# STM32_BOARD_v1a_main.net
KiCad netlist of a schematic drawn in Altium Designer
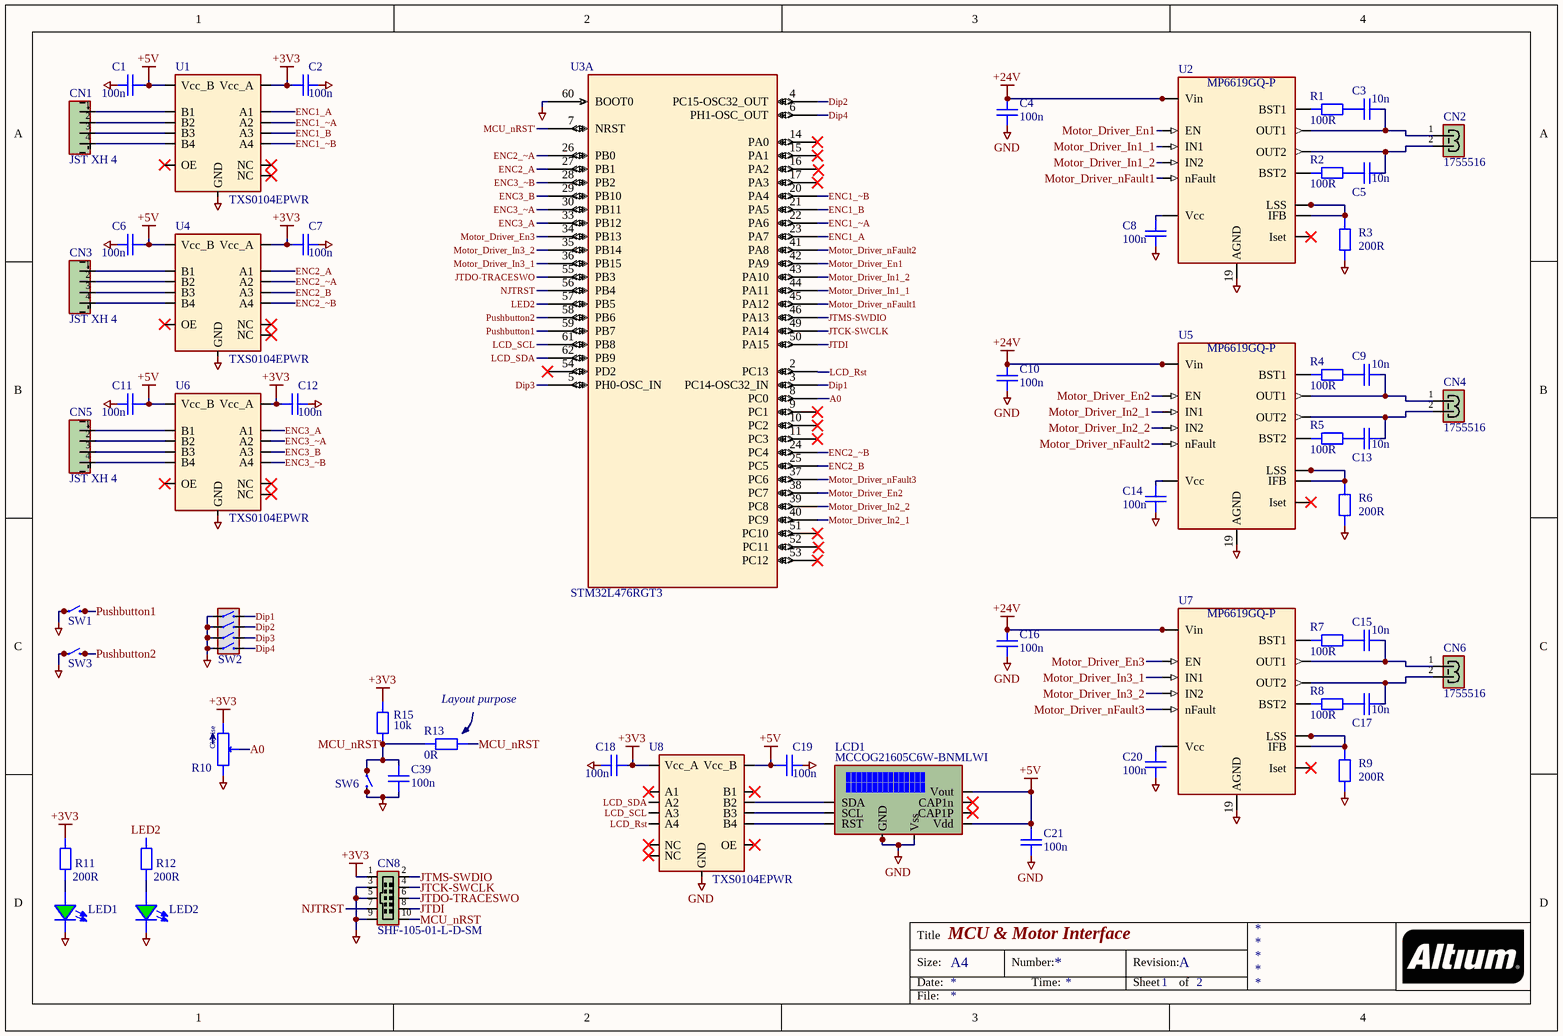
[diagram p0: STM32_BOARD_v1a_main.SchDoc]

(export (version "E")
  (design (tool "Eeschema 10.0.6"))
  (components
    (comp (ref "C1") (value "100n") (footprint "CAP_SMD") (libsource (lib "Miscellanous") (part "C")))
    (comp (ref "C2") (value "100n") (footprint "CAP_SMD") (libsource (lib "Miscellanous") (part "C")))
    (comp (ref "C3") (value "10n") (footprint "CAP_SMD") (libsource (lib "Miscellanous") (part "C")))
    (comp (ref "C4") (value "100n") (footprint "CAP_SMD") (libsource (lib "Miscellanous") (part "C")))
    (comp (ref "C5") (value "10n") (footprint "CAP_SMD") (libsource (lib "Miscellanous") (part "C")))
    (comp (ref "C6") (value "100n") (footprint "CAP_SMD") (libsource (lib "Miscellanous") (part "C")))
    (comp (ref "C7") (value "100n") (footprint "CAP_SMD") (libsource (lib "Miscellanous") (part "C")))
    (comp (ref "C8") (value "100n") (footprint "CAP_SMD") (libsource (lib "Miscellanous") (part "C")))
    (comp (ref "C9") (value "10n") (footprint "CAP_SMD") (libsource (lib "Miscellanous") (part "C")))
    (comp (ref "C10") (value "100n") (footprint "CAP_SMD") (libsource (lib "Miscellanous") (part "C")))
    (comp (ref "C11") (value "100n") (footprint "CAP_SMD") (libsource (lib "Miscellanous") (part "C")))
    (comp (ref "C12") (value "100n") (footprint "CAP_SMD") (libsource (lib "Miscellanous") (part "C")))
    (comp (ref "C13") (value "10n") (footprint "CAP_SMD") (libsource (lib "Miscellanous") (part "C")))
    (comp (ref "C14") (value "100n") (footprint "CAP_SMD") (libsource (lib "Miscellanous") (part "C")))
    (comp (ref "C15") (value "10n") (footprint "CAP_SMD") (libsource (lib "Miscellanous") (part "C")))
    (comp (ref "C16") (value "100n") (footprint "CAP_SMD") (libsource (lib "Miscellanous") (part "C")))
    (comp (ref "C17") (value "10n") (footprint "CAP_SMD") (libsource (lib "Miscellanous") (part "C")))
    (comp (ref "C18") (value "100n") (footprint "CAP_SMD") (libsource (lib "Miscellanous") (part "C")))
    (comp (ref "C19") (value "100n") (footprint "CAP_SMD") (libsource (lib "Miscellanous") (part "C")))
    (comp (ref "C20") (value "100n") (footprint "CAP_SMD") (libsource (lib "Miscellanous") (part "C")))
    (comp (ref "C21") (value "100n") (footprint "CAP_SMD") (libsource (lib "Miscellanous") (part "C")))
    (comp (ref "C39") (value "100n") (footprint "CAP_SMD") (libsource (lib "Miscellanous") (part "C")))
    (comp (ref "CN1")
      (value "JST XH 4")
      (footprint "JST_XH_4-PIN")
      (description "JST XH 4 Pin Connector")
      (fields (field (name "MANUFACTURER") "JASO"))
      (libsource (lib "Connectors") (part "JST_XH_4_PIN"))
    )
    (comp (ref "CN2")
      (value "PHOENIX_CONTACT_2x1_")
      (footprint "1755516")
      (description "Pin header, straight, Straight, 5mm Pitch, 2 Poles, Phoenix Contact")
      (fields (field (name "MANUFACTURER") "Phoenix Contact") (field (name "MFR PART NUM.") "1755516"))
      (libsource (lib "Connectors") (part "PHOENIX_CONTACT_2x1_"))
    )
    (comp (ref "CN3")
      (value "JST XH 4")
      (footprint "JST_XH_4-PIN")
      (description "JST XH 4 Pin Connector")
      (fields (field (name "MANUFACTURER") "JASO"))
      (libsource (lib "Connectors") (part "JST_XH_4_PIN"))
    )
    (comp (ref "CN4")
      (value "PHOENIX_CONTACT_2x1_")
      (footprint "1755516")
      (description "Pin header, straight, Straight, 5mm Pitch, 2 Poles, Phoenix Contact")
      (fields (field (name "MANUFACTURER") "Phoenix Contact") (field (name "MFR PART NUM.") "1755516"))
      (libsource (lib "Connectors") (part "PHOENIX_CONTACT_2x1_"))
    )
    (comp (ref "CN5")
      (value "JST XH 4")
      (footprint "JST_XH_4-PIN")
      (description "JST XH 4 Pin Connector")
      (fields (field (name "MANUFACTURER") "JASO"))
      (libsource (lib "Connectors") (part "JST_XH_4_PIN"))
    )
    (comp (ref "CN6")
      (value "PHOENIX_CONTACT_2x1_")
      (footprint "1755516")
      (description "Pin header, straight, Straight, 5mm Pitch, 2 Poles, Phoenix Contact")
      (fields (field (name "MANUFACTURER") "Phoenix Contact") (field (name "MFR PART NUM.") "1755516"))
      (libsource (lib "Connectors") (part "PHOENIX_CONTACT_2x1_"))
    )
    (comp (ref "CN8")
      (value "SHF-105-01-L-D-SM")
      (footprint "SHF-105-01-L-D-SM")
      (description "Pin Header, Vertical, Wire-to-Board, 1.27 mm, 2 Rows, 10 Contacts, Surface Mount, SHF")
      (fields (field (name "MANUFACTURER") "Samtec"))
      (libsource (lib "Connectors") (part "SHF-105-01-L-D-SM"))
    )
    (comp (ref "LCD1")
      (value "MCCOG21605C6W-BNMLWI")
      (footprint "MCCOG21605C6W-BNMLWI")
      (description "Alphanumeric LCD, 16 x 2, White on Blue, 3V to 5V, I2C, English, Japanese, Transmissive")
      (fields (field (name "MANUFACTURER") "MIDAS"))
      (libsource (lib "Various") (part "MCCOG21605C6W-BNMLWI"))
    )
    (comp (ref "LED1")
      (value "LED_SMD_GREEN")
      (footprint "LED_0805_GREEN")
      (libsource (lib "Miscellanous") (part "LED_SMD_GREEN"))
    )
    (comp (ref "LED2")
      (value "LED_SMD_GREEN")
      (footprint "LED_0805_GREEN")
      (libsource (lib "Miscellanous") (part "LED_SMD_GREEN"))
    )
    (comp (ref "R1") (value "100R") (footprint "RES_0805") (libsource (lib "Miscellanous") (part "R")))
    (comp (ref "R2") (value "100R") (footprint "RES_0805") (libsource (lib "") (part "R_1")))
    (comp (ref "R3") (value "200R") (footprint "RES_0805") (libsource (lib "Miscellanous") (part "R")))
    (comp (ref "R4") (value "100R") (footprint "RES_0805") (libsource (lib "Miscellanous") (part "R")))
    (comp (ref "R5") (value "100R") (footprint "RES_0805") (libsource (lib "") (part "R_1")))
    (comp (ref "R6") (value "200R") (footprint "RES_0805") (libsource (lib "Miscellanous") (part "R")))
    (comp (ref "R7") (value "100R") (footprint "RES_0805") (libsource (lib "Miscellanous") (part "R")))
    (comp (ref "R8") (value "100R") (footprint "RES_0805") (libsource (lib "") (part "R_1")))
    (comp (ref "R9") (value "200R") (footprint "RES_0805") (libsource (lib "Miscellanous") (part "R")))
    (comp (ref "R10")
      (value "TC33X-2-502E")
      (footprint "TC33X-2")
      (description "Trimpot, Single Turn, Cermet, Top Adjust, 5 kohm, Surface Mount, 1 Turns")
      (fields (field (name "MANUFACTURER") "Bourns"))
      (libsource (lib "Various") (part "TC33X-2-502E"))
    )
    (comp (ref "R11") (value "200R") (footprint "RES_0805") (libsource (lib "") (part "R_1")))
    (comp (ref "R12") (value "200R") (footprint "RES_0805") (libsource (lib "") (part "R_1")))
    (comp (ref "R13") (value "0R") (footprint "RES_0805") (libsource (lib "") (part "R_2")))
    (comp (ref "R15") (value "10k") (footprint "RES_0805") (libsource (lib "") (part "R_1")))
    (comp (ref "SW1")
      (value "PTS645SM43SMTR92LFS")
      (footprint "Pushbutton_6x6mm")
      (description "Tactile Switch, PT645, Top Actuated, Surface Mount, Round Button, 160 gf, 50mA at 12VDC")
      (fields (field (name "MANUFACTURER") "C&K Components") (field (name "VOLTAGE") "12V"))
      (libsource (lib "Various") (part "PTS645SM43SMTR92LFS"))
    )
    (comp (ref "SW2")
      (value "A6H-4101")
      (footprint "A6H-4101")
      (description "DIP / SIP Switch, 4 Circuits, Slide, Surface Mount, SPST, 24 VDC, 25 mA")
      (fields (field (name "MANUFACTURER") "Omron") (field (name "VOLTAGE") "24V"))
      (libsource (lib "Various") (part "A6H-4101"))
    )
    (comp (ref "SW3")
      (value "PTS645SM43SMTR92LFS")
      (footprint "Pushbutton_6x6mm")
      (description "Tactile Switch, PT645, Top Actuated, Surface Mount, Round Button, 160 gf, 50mA at 12VDC")
      (fields (field (name "MANUFACTURER") "C&K Components") (field (name "VOLTAGE") "12V"))
      (libsource (lib "Various") (part "PTS645SM43SMTR92LFS"))
    )
    (comp (ref "SW6")
      (value "PTS645SM43SMTR92LFS")
      (footprint "Pushbutton_6x6mm")
      (description "Tactile Switch, PT645, Top Actuated, Surface Mount, Round Button, 160 gf, 50mA at 12VDC")
      (fields (field (name "MANUFACTURER") "C&K Components") (field (name "VOLTAGE") "12V"))
      (libsource (lib "Various") (part "PTS645SM43SMTR92LFS"))
    )
    (comp (ref "U1")
      (value "TXS0104EPWR")
      (footprint "TSOP65P640X120-14N")
      (description "Voltage Level Translator, 4 Input, 50 mA, 4.6 ns, 1.65 V to 5.5 V, TSSOP-14")
      (fields (field (name "MANUFACTURER") "Texas Instruments") (field (name "MFR PART NUM.") "TXS0104EPWR"))
      (libsource (lib "IC_Digital") (part "TXS0104E"))
    )
    (comp (ref "U2")
      (value "MP6619GQ-P")
      (footprint "MP6619GQ-P")
      (description "H-Bridge Motor driver")
      (fields (field (name "MANUFACTURER") "MPS") (field (name "MFR PART NUM") "MP6619GQ-P"))
      (libsource (lib "IC_Digital") (part "MP6619GQ-P"))
    )
    (comp (ref "U3")
      (value "32-bit Microcontroller")
      (footprint "LQFP64_10x10mm")
      (description "STM32 Arm-based 32-bit Microcontroller")
      (fields
        (field (name "MFR PART NUM") "STM32L476RGT3")
        (field (name "MANUFACTURER") "STMicroelectronics")
      )
      (libsource (lib "IC_Digital") (part "STM32L476RGT3"))
    )
    (comp (ref "U4")
      (value "TXS0104EPWR")
      (footprint "TSOP65P640X120-14N")
      (description "Voltage Level Translator, 4 Input, 50 mA, 4.6 ns, 1.65 V to 5.5 V, TSSOP-14")
      (fields (field (name "MANUFACTURER") "Texas Instruments") (field (name "MFR PART NUM.") "TXS0104EPWR"))
      (libsource (lib "IC_Digital") (part "TXS0104E"))
    )
    (comp (ref "U5")
      (value "MP6619GQ-P")
      (footprint "MP6619GQ-P")
      (description "H-Bridge Motor driver")
      (fields (field (name "MANUFACTURER") "MPS") (field (name "MFR PART NUM") "MP6619GQ-P"))
      (libsource (lib "IC_Digital") (part "MP6619GQ-P"))
    )
    (comp (ref "U6")
      (value "TXS0104EPWR")
      (footprint "TSOP65P640X120-14N")
      (description "Voltage Level Translator, 4 Input, 50 mA, 4.6 ns, 1.65 V to 5.5 V, TSSOP-14")
      (fields (field (name "MANUFACTURER") "Texas Instruments") (field (name "MFR PART NUM.") "TXS0104EPWR"))
      (libsource (lib "IC_Digital") (part "TXS0104E"))
    )
    (comp (ref "U7")
      (value "MP6619GQ-P")
      (footprint "MP6619GQ-P")
      (description "H-Bridge Motor driver")
      (fields (field (name "MANUFACTURER") "MPS") (field (name "MFR PART NUM") "MP6619GQ-P"))
      (libsource (lib "IC_Digital") (part "MP6619GQ-P"))
    )
    (comp (ref "U8")
      (value "TXS0104EPWR")
      (footprint "TSOP65P640X120-14N")
      (description "Voltage Level Translator, 4 Input, 50 mA, 4.6 ns, 1.65 V to 5.5 V, TSSOP-14")
      (fields (field (name "MANUFACTURER") "Texas Instruments") (field (name "MFR PART NUM.") "TXS0104EPWR"))
      (libsource (lib "") (part "TXS0104E_1"))
    )
  )
  (nets
    (net (code "1") (name "+3V3") (class "Default")
      (node (ref "C12") (pin "2") (pinfunction "Pin_2_2") (pintype "passive"))
      (node (ref "C18") (pin "2") (pinfunction "Pin_2_2") (pintype "passive"))
      (node (ref "C2") (pin "2") (pinfunction "Pin_2_2") (pintype "passive"))
      (node (ref "C7") (pin "2") (pinfunction "Pin_2_2") (pintype "passive"))
      (node (ref "CN8") (pin "1") (pinfunction "Pin1_1") (pintype "power_in"))
      (node (ref "R10") (pin "3") (pinfunction "Pin_3_3") (pintype "power_in"))
      (node (ref "R11") (pin "2") (pinfunction "Pin_2_2") (pintype "passive"))
      (node (ref "R15") (pin "2") (pinfunction "Pin_2_2") (pintype "passive"))
      (node (ref "U1") (pin "1") (pinfunction "Vcc_A_1") (pintype "power_in"))
      (node (ref "U4") (pin "1") (pinfunction "Vcc_A_1") (pintype "power_in"))
      (node (ref "U6") (pin "1") (pinfunction "Vcc_A_1") (pintype "power_in"))
      (node (ref "U8") (pin "1") (pinfunction "Vcc_A_1") (pintype "power_in"))
    )
    (net (code "2") (name "+5V") (class "Default")
      (node (ref "C1") (pin "2") (pinfunction "Pin_2_2") (pintype "passive"))
      (node (ref "C11") (pin "2") (pinfunction "Pin_2_2") (pintype "passive"))
      (node (ref "C19") (pin "2") (pinfunction "Pin_2_2") (pintype "passive"))
      (node (ref "C21") (pin "2") (pinfunction "Pin_2_2") (pintype "passive"))
      (node (ref "C6") (pin "2") (pinfunction "Pin_2_2") (pintype "passive"))
      (node (ref "LCD1") (pin "1") (pinfunction "Vout_1") (pintype "power_in"))
      (node (ref "LCD1") (pin "4") (pinfunction "Vdd_4") (pintype "power_in"))
      (node (ref "U1") (pin "14") (pinfunction "Vcc_B_14") (pintype "power_in"))
      (node (ref "U4") (pin "14") (pinfunction "Vcc_B_14") (pintype "power_in"))
      (node (ref "U6") (pin "14") (pinfunction "Vcc_B_14") (pintype "power_in"))
      (node (ref "U8") (pin "14") (pinfunction "Vcc_B_14") (pintype "power_in"))
    )
    (net (code "3") (name "+24V") (class "Default")
      (node (ref "C10") (pin "2") (pinfunction "Pin_2_2") (pintype "passive"))
      (node (ref "C16") (pin "2") (pinfunction "Pin_2_2") (pintype "passive"))
      (node (ref "C4") (pin "2") (pinfunction "Pin_2_2") (pintype "passive"))
      (node (ref "U2") (pin "11") (pinfunction "Vin_11") (pintype "power_in"))
      (node (ref "U2") (pin "2") (pinfunction "Vin_2") (pintype "power_in"))
      (node (ref "U5") (pin "11") (pinfunction "Vin_11") (pintype "power_in"))
      (node (ref "U5") (pin "2") (pinfunction "Vin_2") (pintype "power_in"))
      (node (ref "U7") (pin "11") (pinfunction "Vin_11") (pintype "power_in"))
      (node (ref "U7") (pin "2") (pinfunction "Vin_2") (pintype "power_in"))
    )
    (net (code "4") (name "/A0") (class "Default")
      (node (ref "R10") (pin "2") (pinfunction "Pin_2_2") (pintype "power_in"))
      (node (ref "U3") (pin "8") (pinfunction "PC0_8") (pintype "bidirectional"))
    )
    (net (code "5") (name "/Dip1") (class "Default")
      (node (ref "SW2") (pin "8") (pinfunction "Pin_8_8") (pintype "passive"))
      (node (ref "U3") (pin "3") (pinfunction "PC14-OSC32_IN_3") (pintype "bidirectional"))
    )
    (net (code "6") (name "/Dip2") (class "Default")
      (node (ref "SW2") (pin "7") (pinfunction "Pin_7_7") (pintype "passive"))
      (node (ref "U3") (pin "4") (pinfunction "PC15-OSC32_OUT_4") (pintype "bidirectional"))
    )
    (net (code "7") (name "/Dip3") (class "Default")
      (node (ref "SW2") (pin "6") (pinfunction "Pin_6_6") (pintype "passive"))
      (node (ref "U3") (pin "5") (pinfunction "PH0-OSC_IN_5") (pintype "bidirectional"))
    )
    (net (code "8") (name "/Dip4") (class "Default")
      (node (ref "SW2") (pin "5") (pinfunction "Pin_5_5") (pintype "passive"))
      (node (ref "U3") (pin "6") (pinfunction "PH1-OSC_OUT_6") (pintype "bidirectional"))
    )
    (net (code "9") (name "/ENC1_A") (class "Default")
      (node (ref "U1") (pin "2") (pinfunction "A1_2") (pintype "power_in"))
      (node (ref "U3") (pin "23") (pinfunction "PA7_23") (pintype "bidirectional"))
    )
    (net (code "10") (name "/ENC1_B") (class "Default")
      (node (ref "U1") (pin "4") (pinfunction "A3_4") (pintype "power_in"))
      (node (ref "U3") (pin "21") (pinfunction "PA5_21") (pintype "bidirectional"))
    )
    (net (code "11") (name "/ENC1_~A") (class "Default")
      (node (ref "U1") (pin "3") (pinfunction "A2_3") (pintype "power_in"))
      (node (ref "U3") (pin "22") (pinfunction "PA6_22") (pintype "bidirectional"))
    )
    (net (code "12") (name "/ENC1_~B") (class "Default")
      (node (ref "U1") (pin "5") (pinfunction "A4_5") (pintype "power_in"))
      (node (ref "U3") (pin "20") (pinfunction "PA4_20") (pintype "bidirectional"))
    )
    (net (code "13") (name "/ENC2_A") (class "Default")
      (node (ref "U3") (pin "27") (pinfunction "PB1_27") (pintype "bidirectional"))
      (node (ref "U4") (pin "2") (pinfunction "A1_2") (pintype "power_in"))
    )
    (net (code "14") (name "/ENC2_B") (class "Default")
      (node (ref "U3") (pin "25") (pinfunction "PC5_25") (pintype "bidirectional"))
      (node (ref "U4") (pin "4") (pinfunction "A3_4") (pintype "power_in"))
    )
    (net (code "15") (name "/ENC2_~A") (class "Default")
      (node (ref "U3") (pin "26") (pinfunction "PB0_26") (pintype "bidirectional"))
      (node (ref "U4") (pin "3") (pinfunction "A2_3") (pintype "power_in"))
    )
    (net (code "16") (name "/ENC2_~B") (class "Default")
      (node (ref "U3") (pin "24") (pinfunction "PC4_24") (pintype "bidirectional"))
      (node (ref "U4") (pin "5") (pinfunction "A4_5") (pintype "power_in"))
    )
    (net (code "17") (name "/ENC3_A") (class "Default")
      (node (ref "U3") (pin "33") (pinfunction "PB12_33") (pintype "bidirectional"))
      (node (ref "U6") (pin "2") (pinfunction "A1_2") (pintype "power_in"))
    )
    (net (code "18") (name "/ENC3_B") (class "Default")
      (node (ref "U3") (pin "29") (pinfunction "PB10_29") (pintype "bidirectional"))
      (node (ref "U6") (pin "4") (pinfunction "A3_4") (pintype "power_in"))
    )
    (net (code "19") (name "/ENC3_~A") (class "Default")
      (node (ref "U3") (pin "30") (pinfunction "PB11_30") (pintype "bidirectional"))
      (node (ref "U6") (pin "3") (pinfunction "A2_3") (pintype "power_in"))
    )
    (net (code "20") (name "/ENC3_~B") (class "Default")
      (node (ref "U3") (pin "28") (pinfunction "PB2_28") (pintype "bidirectional"))
      (node (ref "U6") (pin "5") (pinfunction "A4_5") (pintype "power_in"))
    )
    (net (code "21") (name "/JTCK-SWCLK") (class "Default")
      (node (ref "CN8") (pin "4") (pinfunction "4_4") (pintype "power_in"))
      (node (ref "U3") (pin "49") (pinfunction "PA14_49") (pintype "bidirectional"))
    )
    (net (code "22") (name "/JTDI") (class "Default")
      (node (ref "CN8") (pin "8") (pinfunction "8_8") (pintype "power_in"))
      (node (ref "U3") (pin "50") (pinfunction "PA15_50") (pintype "bidirectional"))
    )
    (net (code "23") (name "/JTDO-TRACESWO") (class "Default")
      (node (ref "CN8") (pin "6") (pinfunction "6_6") (pintype "power_in"))
      (node (ref "U3") (pin "55") (pinfunction "PB3_55") (pintype "bidirectional"))
    )
    (net (code "24") (name "/JTMS-SWDIO") (class "Default")
      (node (ref "CN8") (pin "2") (pinfunction "Pin2_2") (pintype "power_in"))
      (node (ref "U3") (pin "46") (pinfunction "PA13_46") (pintype "bidirectional"))
    )
    (net (code "25") (name "/LCD_Rst") (class "Default")
      (node (ref "U3") (pin "2") (pinfunction "PC13_2") (pintype "bidirectional"))
      (node (ref "U8") (pin "5") (pinfunction "A4_5") (pintype "power_in"))
    )
    (net (code "26") (name "/LCD_SCL") (class "Default")
      (node (ref "U3") (pin "61") (pinfunction "PB8_61") (pintype "bidirectional"))
      (node (ref "U8") (pin "4") (pinfunction "A3_4") (pintype "power_in"))
    )
    (net (code "27") (name "/LCD_SDA") (class "Default")
      (node (ref "U3") (pin "62") (pinfunction "PB9_62") (pintype "bidirectional"))
      (node (ref "U8") (pin "3") (pinfunction "A2_3") (pintype "power_in"))
    )
    (net (code "28") (name "/LED2") (class "Default")
      (node (ref "R12") (pin "2") (pinfunction "Pin_2_2") (pintype "passive"))
      (node (ref "U3") (pin "57") (pinfunction "PB5_57") (pintype "bidirectional"))
    )
    (net (code "29") (name "/MCU_nRST") (class "Default")
      (node (ref "CN8") (pin "10") (pinfunction "10_10") (pintype "power_in"))
      (node (ref "R13") (pin "1") (pinfunction "Pin_1_1") (pintype "passive"))
    )
    (net (code "30") (name "/MCU_nRST'") (class "Default")
      (node (ref "C39") (pin "2") (pinfunction "Pin_2_2") (pintype "passive"))
      (node (ref "R13") (pin "2") (pinfunction "Pin_2_2") (pintype "passive"))
      (node (ref "R15") (pin "1") (pinfunction "Pin_1_1") (pintype "passive"))
      (node (ref "SW6") (pin "1") (pinfunction "Pin_1_1") (pintype "passive"))
      (node (ref "SW6") (pin "2") (pinfunction "Pin_2_2") (pintype "passive"))
      (node (ref "U3") (pin "7") (pinfunction "NRST_7") (pintype "bidirectional"))
    )
    (net (code "31") (name "/Motor_Driver_En1") (class "Default")
      (node (ref "U2") (pin "5") (pinfunction "EN_5") (pintype "input"))
      (node (ref "U3") (pin "42") (pinfunction "PA9_42") (pintype "bidirectional"))
    )
    (net (code "32") (name "/Motor_Driver_En2") (class "Default")
      (node (ref "U3") (pin "38") (pinfunction "PC7_38") (pintype "bidirectional"))
      (node (ref "U5") (pin "5") (pinfunction "EN_5") (pintype "input"))
    )
    (net (code "33") (name "/Motor_Driver_En3") (class "Default")
      (node (ref "U3") (pin "34") (pinfunction "PB13_34") (pintype "bidirectional"))
      (node (ref "U7") (pin "5") (pinfunction "EN_5") (pintype "input"))
    )
    (net (code "34") (name "/Motor_Driver_In1_1") (class "Default")
      (node (ref "U2") (pin "15") (pinfunction "IN1_15") (pintype "input"))
      (node (ref "U3") (pin "44") (pinfunction "PA11_44") (pintype "bidirectional"))
    )
    (net (code "35") (name "/Motor_Driver_In1_2") (class "Default")
      (node (ref "U2") (pin "16") (pinfunction "IN2_16") (pintype "input"))
      (node (ref "U3") (pin "43") (pinfunction "PA10_43") (pintype "bidirectional"))
    )
    (net (code "36") (name "/Motor_Driver_In2_1") (class "Default")
      (node (ref "U3") (pin "40") (pinfunction "PC9_40") (pintype "bidirectional"))
      (node (ref "U5") (pin "15") (pinfunction "IN1_15") (pintype "input"))
    )
    (net (code "37") (name "/Motor_Driver_In2_2") (class "Default")
      (node (ref "U3") (pin "39") (pinfunction "PC8_39") (pintype "bidirectional"))
      (node (ref "U5") (pin "16") (pinfunction "IN2_16") (pintype "input"))
    )
    (net (code "38") (name "/Motor_Driver_In3_1") (class "Default")
      (node (ref "U3") (pin "36") (pinfunction "PB15_36") (pintype "bidirectional"))
      (node (ref "U7") (pin "15") (pinfunction "IN1_15") (pintype "input"))
    )
    (net (code "39") (name "/Motor_Driver_In3_2") (class "Default")
      (node (ref "U3") (pin "35") (pinfunction "PB14_35") (pintype "bidirectional"))
      (node (ref "U7") (pin "16") (pinfunction "IN2_16") (pintype "input"))
    )
    (net (code "40") (name "/Motor_Driver_nFault1") (class "Default")
      (node (ref "U2") (pin "13") (pinfunction "nFault_13") (pintype "input"))
      (node (ref "U3") (pin "45") (pinfunction "PA12_45") (pintype "bidirectional"))
    )
    (net (code "41") (name "/Motor_Driver_nFault2") (class "Default")
      (node (ref "U3") (pin "41") (pinfunction "PA8_41") (pintype "bidirectional"))
      (node (ref "U5") (pin "13") (pinfunction "nFault_13") (pintype "input"))
    )
    (net (code "42") (name "/Motor_Driver_nFault3") (class "Default")
      (node (ref "U3") (pin "37") (pinfunction "PC6_37") (pintype "bidirectional"))
      (node (ref "U7") (pin "13") (pinfunction "nFault_13") (pintype "input"))
    )
    (net (code "43") (name "/NJTRST") (class "Default")
      (node (ref "CN8") (pin "7") (pinfunction "7_7") (pintype "power_in"))
      (node (ref "U3") (pin "56") (pinfunction "PB4_56") (pintype "bidirectional"))
    )
    (net (code "44") (name "/Pushbutton1") (class "Default")
      (node (ref "SW1") (pin "3") (pinfunction "Pin_3_3") (pintype "passive"))
      (node (ref "SW1") (pin "4") (pinfunction "Pin_4_4") (pintype "passive"))
      (node (ref "U3") (pin "59") (pinfunction "PB7_59") (pintype "bidirectional"))
    )
    (net (code "45") (name "/Pushbutton2") (class "Default")
      (node (ref "SW3") (pin "3") (pinfunction "Pin_3_3") (pintype "passive"))
      (node (ref "SW3") (pin "4") (pinfunction "Pin_4_4") (pintype "passive"))
      (node (ref "U3") (pin "58") (pinfunction "PB6_58") (pintype "bidirectional"))
    )
    (net (code "46") (name "GND") (class "Default")
      (node (ref "C1") (pin "1") (pinfunction "Pin_1_1") (pintype "passive"))
      (node (ref "C10") (pin "1") (pinfunction "Pin_1_1") (pintype "passive"))
      (node (ref "C11") (pin "1") (pinfunction "Pin_1_1") (pintype "passive"))
      (node (ref "C12") (pin "1") (pinfunction "Pin_1_1") (pintype "passive"))
      (node (ref "C14") (pin "1") (pinfunction "Pin_1_1") (pintype "passive"))
      (node (ref "C16") (pin "1") (pinfunction "Pin_1_1") (pintype "passive"))
      (node (ref "C18") (pin "1") (pinfunction "Pin_1_1") (pintype "passive"))
      (node (ref "C19") (pin "1") (pinfunction "Pin_1_1") (pintype "passive"))
      (node (ref "C2") (pin "1") (pinfunction "Pin_1_1") (pintype "passive"))
      (node (ref "C20") (pin "1") (pinfunction "Pin_1_1") (pintype "passive"))
      (node (ref "C21") (pin "1") (pinfunction "Pin_1_1") (pintype "passive"))
      (node (ref "C39") (pin "1") (pinfunction "Pin_1_1") (pintype "passive"))
      (node (ref "C4") (pin "1") (pinfunction "Pin_1_1") (pintype "passive"))
      (node (ref "C6") (pin "1") (pinfunction "Pin_1_1") (pintype "passive"))
      (node (ref "C7") (pin "1") (pinfunction "Pin_1_1") (pintype "passive"))
      (node (ref "C8") (pin "1") (pinfunction "Pin_1_1") (pintype "passive"))
      (node (ref "CN8") (pin "3") (pinfunction "3_3") (pintype "power_in"))
      (node (ref "CN8") (pin "5") (pinfunction "5_5") (pintype "power_in"))
      (node (ref "CN8") (pin "9") (pinfunction "9_9") (pintype "power_in"))
      (node (ref "LCD1") (pin "5") (pinfunction "Vss_5") (pintype "power_in"))
      (node (ref "LCD1") (pin "G1") (pinfunction "GND_G1") (pintype "power_in"))
      (node (ref "LCD1") (pin "G2") (pinfunction "GND_G2") (pintype "power_in"))
      (node (ref "LED1") (pin "2") (pinfunction "C_2") (pintype "passive"))
      (node (ref "LED2") (pin "2") (pinfunction "C_2") (pintype "passive"))
      (node (ref "R10") (pin "1") (pinfunction "Pin_1_1") (pintype "power_in"))
      (node (ref "R3") (pin "1") (pinfunction "Pin_1_1") (pintype "passive"))
      (node (ref "R6") (pin "1") (pinfunction "Pin_1_1") (pintype "passive"))
      (node (ref "R9") (pin "1") (pinfunction "Pin_1_1") (pintype "passive"))
      (node (ref "SW1") (pin "1") (pinfunction "Pin_1_1") (pintype "passive"))
      (node (ref "SW1") (pin "2") (pinfunction "Pin_2_2") (pintype "passive"))
      (node (ref "SW2") (pin "1") (pinfunction "Pin_1_1") (pintype "passive"))
      (node (ref "SW2") (pin "2") (pinfunction "Pin_2_2") (pintype "passive"))
      (node (ref "SW2") (pin "3") (pinfunction "Pin_3_3") (pintype "passive"))
      (node (ref "SW2") (pin "4") (pinfunction "Pin_4_4") (pintype "passive"))
      (node (ref "SW3") (pin "1") (pinfunction "Pin_1_1") (pintype "passive"))
      (node (ref "SW3") (pin "2") (pinfunction "Pin_2_2") (pintype "passive"))
      (node (ref "SW6") (pin "3") (pinfunction "Pin_3_3") (pintype "passive"))
      (node (ref "SW6") (pin "4") (pinfunction "Pin_4_4") (pintype "passive"))
      (node (ref "U1") (pin "7") (pinfunction "GND_7") (pintype "power_in"))
      (node (ref "U2") (pin "19") (pinfunction "AGND_19") (pintype "passive"))
      (node (ref "U3") (pin "60") (pinfunction "BOOT0_60") (pintype "input"))
      (node (ref "U4") (pin "7") (pinfunction "GND_7") (pintype "power_in"))
      (node (ref "U5") (pin "19") (pinfunction "AGND_19") (pintype "passive"))
      (node (ref "U6") (pin "7") (pinfunction "GND_7") (pintype "power_in"))
      (node (ref "U7") (pin "19") (pinfunction "AGND_19") (pintype "passive"))
      (node (ref "U8") (pin "7") (pinfunction "GND_7") (pintype "power_in"))
    )
    (net (code "47") (name "Net-(C3-Pin_1)") (class "Default")
      (node (ref "C3") (pin "1") (pinfunction "Pin_1_1") (pintype "passive"))
      (node (ref "R1") (pin "2") (pinfunction "Pin_2_2") (pintype "passive"))
    )
    (net (code "48") (name "Net-(C3-Pin_2)") (class "Default")
      (node (ref "C3") (pin "2") (pinfunction "Pin_2_2") (pintype "passive"))
      (node (ref "CN2") (pin "1") (pinfunction "Pin_1_1") (pintype "passive"))
      (node (ref "U2") (pin "10") (pinfunction "OUT1_10") (pintype "output"))
    )
    (net (code "49") (name "Net-(C5-Pin_1)") (class "Default")
      (node (ref "C5") (pin "1") (pinfunction "Pin_1_1") (pintype "passive"))
      (node (ref "R2") (pin "2") (pinfunction "Pin_2_2") (pintype "passive"))
    )
    (net (code "50") (name "Net-(C5-Pin_2)") (class "Default")
      (node (ref "C5") (pin "2") (pinfunction "Pin_2_2") (pintype "passive"))
      (node (ref "CN2") (pin "2") (pinfunction "Pin_2_2") (pintype "passive"))
      (node (ref "U2") (pin "3") (pinfunction "OUT2_3") (pintype "output"))
    )
    (net (code "51") (name "Net-(C8-Pin_2)") (class "Default")
      (node (ref "C8") (pin "2") (pinfunction "Pin_2_2") (pintype "passive"))
      (node (ref "U2") (pin "14") (pinfunction "Vcc_14") (pintype "power_in"))
    )
    (net (code "52") (name "Net-(C9-Pin_1)") (class "Default")
      (node (ref "C9") (pin "1") (pinfunction "Pin_1_1") (pintype "passive"))
      (node (ref "R4") (pin "2") (pinfunction "Pin_2_2") (pintype "passive"))
    )
    (net (code "53") (name "Net-(C9-Pin_2)") (class "Default")
      (node (ref "C9") (pin "2") (pinfunction "Pin_2_2") (pintype "passive"))
      (node (ref "CN4") (pin "1") (pinfunction "Pin_1_1") (pintype "passive"))
      (node (ref "U5") (pin "10") (pinfunction "OUT1_10") (pintype "output"))
    )
    (net (code "54") (name "Net-(C13-Pin_1)") (class "Default")
      (node (ref "C13") (pin "1") (pinfunction "Pin_1_1") (pintype "passive"))
      (node (ref "R5") (pin "2") (pinfunction "Pin_2_2") (pintype "passive"))
    )
    (net (code "55") (name "Net-(C13-Pin_2)") (class "Default")
      (node (ref "C13") (pin "2") (pinfunction "Pin_2_2") (pintype "passive"))
      (node (ref "CN4") (pin "2") (pinfunction "Pin_2_2") (pintype "passive"))
      (node (ref "U5") (pin "3") (pinfunction "OUT2_3") (pintype "output"))
    )
    (net (code "56") (name "Net-(C14-Pin_2)") (class "Default")
      (node (ref "C14") (pin "2") (pinfunction "Pin_2_2") (pintype "passive"))
      (node (ref "U5") (pin "14") (pinfunction "Vcc_14") (pintype "power_in"))
    )
    (net (code "57") (name "Net-(C15-Pin_1)") (class "Default")
      (node (ref "C15") (pin "1") (pinfunction "Pin_1_1") (pintype "passive"))
      (node (ref "R7") (pin "2") (pinfunction "Pin_2_2") (pintype "passive"))
    )
    (net (code "58") (name "Net-(C15-Pin_2)") (class "Default")
      (node (ref "C15") (pin "2") (pinfunction "Pin_2_2") (pintype "passive"))
      (node (ref "CN6") (pin "1") (pinfunction "Pin_1_1") (pintype "passive"))
      (node (ref "U7") (pin "10") (pinfunction "OUT1_10") (pintype "output"))
    )
    (net (code "59") (name "Net-(C17-Pin_1)") (class "Default")
      (node (ref "C17") (pin "1") (pinfunction "Pin_1_1") (pintype "passive"))
      (node (ref "R8") (pin "2") (pinfunction "Pin_2_2") (pintype "passive"))
    )
    (net (code "60") (name "Net-(C17-Pin_2)") (class "Default")
      (node (ref "C17") (pin "2") (pinfunction "Pin_2_2") (pintype "passive"))
      (node (ref "CN6") (pin "2") (pinfunction "Pin_2_2") (pintype "passive"))
      (node (ref "U7") (pin "3") (pinfunction "OUT2_3") (pintype "output"))
    )
    (net (code "61") (name "Net-(C20-Pin_2)") (class "Default")
      (node (ref "C20") (pin "2") (pinfunction "Pin_2_2") (pintype "passive"))
      (node (ref "U7") (pin "14") (pinfunction "Vcc_14") (pintype "power_in"))
    )
    (net (code "62") (name "Net-(CN1-Pin_1)") (class "Default")
      (node (ref "CN1") (pin "1") (pinfunction "Pin_1_1") (pintype "passive"))
      (node (ref "U1") (pin "13") (pinfunction "B1_13") (pintype "power_in"))
    )
    (net (code "63") (name "Net-(CN1-Pin_2)") (class "Default")
      (node (ref "CN1") (pin "2") (pinfunction "Pin_2_2") (pintype "passive"))
      (node (ref "U1") (pin "12") (pinfunction "B2_12") (pintype "power_in"))
    )
    (net (code "64") (name "Net-(CN1-Pin_3)") (class "Default")
      (node (ref "CN1") (pin "3") (pinfunction "Pin_3_3") (pintype "passive"))
      (node (ref "U1") (pin "11") (pinfunction "B3_11") (pintype "power_in"))
    )
    (net (code "65") (name "Net-(CN1-Pin_4)") (class "Default")
      (node (ref "CN1") (pin "4") (pinfunction "Pin_4_4") (pintype "passive"))
      (node (ref "U1") (pin "10") (pinfunction "B4_10") (pintype "power_in"))
    )
    (net (code "66") (name "Net-(CN3-Pin_1)") (class "Default")
      (node (ref "CN3") (pin "1") (pinfunction "Pin_1_1") (pintype "passive"))
      (node (ref "U4") (pin "13") (pinfunction "B1_13") (pintype "power_in"))
    )
    (net (code "67") (name "Net-(CN3-Pin_2)") (class "Default")
      (node (ref "CN3") (pin "2") (pinfunction "Pin_2_2") (pintype "passive"))
      (node (ref "U4") (pin "12") (pinfunction "B2_12") (pintype "power_in"))
    )
    (net (code "68") (name "Net-(CN3-Pin_3)") (class "Default")
      (node (ref "CN3") (pin "3") (pinfunction "Pin_3_3") (pintype "passive"))
      (node (ref "U4") (pin "11") (pinfunction "B3_11") (pintype "power_in"))
    )
    (net (code "69") (name "Net-(CN3-Pin_4)") (class "Default")
      (node (ref "CN3") (pin "4") (pinfunction "Pin_4_4") (pintype "passive"))
      (node (ref "U4") (pin "10") (pinfunction "B4_10") (pintype "power_in"))
    )
    (net (code "70") (name "Net-(CN5-Pin_1)") (class "Default")
      (node (ref "CN5") (pin "1") (pinfunction "Pin_1_1") (pintype "passive"))
      (node (ref "U6") (pin "13") (pinfunction "B1_13") (pintype "power_in"))
    )
    (net (code "71") (name "Net-(CN5-Pin_2)") (class "Default")
      (node (ref "CN5") (pin "2") (pinfunction "Pin_2_2") (pintype "passive"))
      (node (ref "U6") (pin "12") (pinfunction "B2_12") (pintype "power_in"))
    )
    (net (code "72") (name "Net-(CN5-Pin_3)") (class "Default")
      (node (ref "CN5") (pin "3") (pinfunction "Pin_3_3") (pintype "passive"))
      (node (ref "U6") (pin "11") (pinfunction "B3_11") (pintype "power_in"))
    )
    (net (code "73") (name "Net-(CN5-Pin_4)") (class "Default")
      (node (ref "CN5") (pin "4") (pinfunction "Pin_4_4") (pintype "passive"))
      (node (ref "U6") (pin "10") (pinfunction "B4_10") (pintype "power_in"))
    )
    (net (code "74") (name "Net-(LCD1-RST)") (class "Default")
      (node (ref "LCD1") (pin "8") (pinfunction "RST_8") (pintype "input"))
      (node (ref "U8") (pin "10") (pinfunction "B4_10") (pintype "power_in"))
    )
    (net (code "75") (name "Net-(LCD1-SCL)") (class "Default")
      (node (ref "LCD1") (pin "7") (pinfunction "SCL_7") (pintype "bidirectional"))
      (node (ref "U8") (pin "11") (pinfunction "B3_11") (pintype "power_in"))
    )
    (net (code "76") (name "Net-(LCD1-SDA)") (class "Default")
      (node (ref "LCD1") (pin "6") (pinfunction "SDA_6") (pintype "bidirectional"))
      (node (ref "U8") (pin "12") (pinfunction "B2_12") (pintype "power_in"))
    )
    (net (code "77") (name "Net-(LED1-A)") (class "Default")
      (node (ref "LED1") (pin "1") (pinfunction "A_1") (pintype "passive"))
      (node (ref "R11") (pin "1") (pinfunction "Pin_1_1") (pintype "passive"))
    )
    (net (code "78") (name "Net-(LED2-A)") (class "Default")
      (node (ref "LED2") (pin "1") (pinfunction "A_1") (pintype "passive"))
      (node (ref "R12") (pin "1") (pinfunction "Pin_1_1") (pintype "passive"))
    )
    (net (code "79") (name "Net-(R1-Pin_1)") (class "Default")
      (node (ref "R1") (pin "1") (pinfunction "Pin_1_1") (pintype "passive"))
      (node (ref "U2") (pin "9") (pinfunction "BST1_9") (pintype "passive"))
    )
    (net (code "80") (name "Net-(R2-Pin_1)") (class "Default")
      (node (ref "R2") (pin "1") (pinfunction "Pin_1_1") (pintype "passive"))
      (node (ref "U2") (pin "4") (pinfunction "BST2_4") (pintype "passive"))
    )
    (net (code "81") (name "Net-(R3-Pin_2)") (class "Default")
      (node (ref "R3") (pin "2") (pinfunction "Pin_2_2") (pintype "passive"))
      (node (ref "U2") (pin "1") (pinfunction "IFB_1") (pintype "passive"))
      (node (ref "U2") (pin "6") (pinfunction "LSS_6") (pintype "passive"))
      (node (ref "U2") (pin "7") (pinfunction "LSS_7") (pintype "passive"))
      (node (ref "U2") (pin "8") (pinfunction "LSS_8") (pintype "passive"))
    )
    (net (code "82") (name "Net-(R4-Pin_1)") (class "Default")
      (node (ref "R4") (pin "1") (pinfunction "Pin_1_1") (pintype "passive"))
      (node (ref "U5") (pin "9") (pinfunction "BST1_9") (pintype "passive"))
    )
    (net (code "83") (name "Net-(R5-Pin_1)") (class "Default")
      (node (ref "R5") (pin "1") (pinfunction "Pin_1_1") (pintype "passive"))
      (node (ref "U5") (pin "4") (pinfunction "BST2_4") (pintype "passive"))
    )
    (net (code "84") (name "Net-(R6-Pin_2)") (class "Default")
      (node (ref "R6") (pin "2") (pinfunction "Pin_2_2") (pintype "passive"))
      (node (ref "U5") (pin "1") (pinfunction "IFB_1") (pintype "passive"))
      (node (ref "U5") (pin "6") (pinfunction "LSS_6") (pintype "passive"))
      (node (ref "U5") (pin "7") (pinfunction "LSS_7") (pintype "passive"))
      (node (ref "U5") (pin "8") (pinfunction "LSS_8") (pintype "passive"))
    )
    (net (code "85") (name "Net-(R7-Pin_1)") (class "Default")
      (node (ref "R7") (pin "1") (pinfunction "Pin_1_1") (pintype "passive"))
      (node (ref "U7") (pin "9") (pinfunction "BST1_9") (pintype "passive"))
    )
    (net (code "86") (name "Net-(R8-Pin_1)") (class "Default")
      (node (ref "R8") (pin "1") (pinfunction "Pin_1_1") (pintype "passive"))
      (node (ref "U7") (pin "4") (pinfunction "BST2_4") (pintype "passive"))
    )
    (net (code "87") (name "Net-(R9-Pin_2)") (class "Default")
      (node (ref "R9") (pin "2") (pinfunction "Pin_2_2") (pintype "passive"))
      (node (ref "U7") (pin "1") (pinfunction "IFB_1") (pintype "passive"))
      (node (ref "U7") (pin "6") (pinfunction "LSS_6") (pintype "passive"))
      (node (ref "U7") (pin "7") (pinfunction "LSS_7") (pintype "passive"))
      (node (ref "U7") (pin "8") (pinfunction "LSS_8") (pintype "passive"))
    )
    (net (code "88") (name "unconnected-(LCD1-CAP1P-Pad3)") (class "Default")
      (node (ref "LCD1") (pin "3") (pinfunction "CAP1P_3") (pintype "power_in+no_connect"))
    )
    (net (code "89") (name "unconnected-(LCD1-CAP1n-Pad2)") (class "Default")
      (node (ref "LCD1") (pin "2") (pinfunction "CAP1n_2") (pintype "power_in+no_connect"))
    )
    (net (code "90") (name "unconnected-(U1-NC-Pad6)") (class "Default")
      (node (ref "U1") (pin "6") (pinfunction "NC_6") (pintype "power_in+no_connect"))
    )
    (net (code "91") (name "unconnected-(U1-NC-Pad9)") (class "Default")
      (node (ref "U1") (pin "9") (pinfunction "NC_9") (pintype "power_in+no_connect"))
    )
    (net (code "92") (name "unconnected-(U1-OE-Pad8)") (class "Default")
      (node (ref "U1") (pin "8") (pinfunction "OE_8") (pintype "power_in+no_connect"))
    )
    (net (code "93") (name "unconnected-(U2-Iset-Pad17)") (class "Default")
      (node (ref "U2") (pin "17") (pinfunction "Iset_17") (pintype "passive+no_connect"))
    )
    (net (code "94") (name "unconnected-(U3A-PA0-Pad14)") (class "Default")
      (node (ref "U3") (pin "14") (pinfunction "PA0_14") (pintype "bidirectional+no_connect"))
    )
    (net (code "95") (name "unconnected-(U3A-PA1-Pad15)") (class "Default")
      (node (ref "U3") (pin "15") (pinfunction "PA1_15") (pintype "bidirectional+no_connect"))
    )
    (net (code "96") (name "unconnected-(U3A-PA2-Pad16)") (class "Default")
      (node (ref "U3") (pin "16") (pinfunction "PA2_16") (pintype "bidirectional"))
    )
    (net (code "97") (name "unconnected-(U3A-PA3-Pad17)") (class "Default")
      (node (ref "U3") (pin "17") (pinfunction "PA3_17") (pintype "bidirectional+no_connect"))
    )
    (net (code "98") (name "unconnected-(U3A-PC1-Pad9)") (class "Default")
      (node (ref "U3") (pin "9") (pinfunction "PC1_9") (pintype "bidirectional+no_connect"))
    )
    (net (code "99") (name "unconnected-(U3A-PC2-Pad10)") (class "Default")
      (node (ref "U3") (pin "10") (pinfunction "PC2_10") (pintype "bidirectional+no_connect"))
    )
    (net (code "100") (name "unconnected-(U3A-PC3-Pad11)") (class "Default")
      (node (ref "U3") (pin "11") (pinfunction "PC3_11") (pintype "bidirectional+no_connect"))
    )
    (net (code "101") (name "unconnected-(U3A-PC10-Pad51)") (class "Default")
      (node (ref "U3") (pin "51") (pinfunction "PC10_51") (pintype "bidirectional+no_connect"))
    )
    (net (code "102") (name "unconnected-(U3A-PC11-Pad52)") (class "Default")
      (node (ref "U3") (pin "52") (pinfunction "PC11_52") (pintype "bidirectional"))
    )
    (net (code "103") (name "unconnected-(U3A-PC12-Pad53)") (class "Default")
      (node (ref "U3") (pin "53") (pinfunction "PC12_53") (pintype "bidirectional+no_connect"))
    )
    (net (code "104") (name "unconnected-(U3A-PD2-Pad54)") (class "Default")
      (node (ref "U3") (pin "54") (pinfunction "PD2_54") (pintype "bidirectional+no_connect"))
    )
    (net (code "105") (name "unconnected-(U4-NC-Pad6)") (class "Default")
      (node (ref "U4") (pin "6") (pinfunction "NC_6") (pintype "power_in+no_connect"))
    )
    (net (code "106") (name "unconnected-(U4-NC-Pad9)") (class "Default")
      (node (ref "U4") (pin "9") (pinfunction "NC_9") (pintype "power_in+no_connect"))
    )
    (net (code "107") (name "unconnected-(U4-OE-Pad8)") (class "Default")
      (node (ref "U4") (pin "8") (pinfunction "OE_8") (pintype "power_in+no_connect"))
    )
    (net (code "108") (name "unconnected-(U5-Iset-Pad17)") (class "Default")
      (node (ref "U5") (pin "17") (pinfunction "Iset_17") (pintype "passive+no_connect"))
    )
    (net (code "109") (name "unconnected-(U6-NC-Pad6)") (class "Default")
      (node (ref "U6") (pin "6") (pinfunction "NC_6") (pintype "power_in+no_connect"))
    )
    (net (code "110") (name "unconnected-(U6-NC-Pad9)") (class "Default")
      (node (ref "U6") (pin "9") (pinfunction "NC_9") (pintype "power_in+no_connect"))
    )
    (net (code "111") (name "unconnected-(U6-OE-Pad8)") (class "Default")
      (node (ref "U6") (pin "8") (pinfunction "OE_8") (pintype "power_in+no_connect"))
    )
    (net (code "112") (name "unconnected-(U7-Iset-Pad17)") (class "Default")
      (node (ref "U7") (pin "17") (pinfunction "Iset_17") (pintype "passive+no_connect"))
    )
    (net (code "113") (name "unconnected-(U8-A1-Pad2)") (class "Default")
      (node (ref "U8") (pin "2") (pinfunction "A1_2") (pintype "power_in+no_connect"))
    )
    (net (code "114") (name "unconnected-(U8-B1-Pad13)") (class "Default")
      (node (ref "U8") (pin "13") (pinfunction "B1_13") (pintype "power_in+no_connect"))
    )
    (net (code "115") (name "unconnected-(U8-NC-Pad6)") (class "Default")
      (node (ref "U8") (pin "6") (pinfunction "NC_6") (pintype "power_in+no_connect"))
    )
    (net (code "116") (name "unconnected-(U8-NC-Pad9)") (class "Default")
      (node (ref "U8") (pin "9") (pinfunction "NC_9") (pintype "power_in+no_connect"))
    )
    (net (code "117") (name "unconnected-(U8-OE-Pad8)") (class "Default")
      (node (ref "U8") (pin "8") (pinfunction "OE_8") (pintype "power_in+no_connect"))
    )
  )
)
